# senseBox-HDC1080_v22.net
KiCad netlist of a schematic drawn in EAGLE
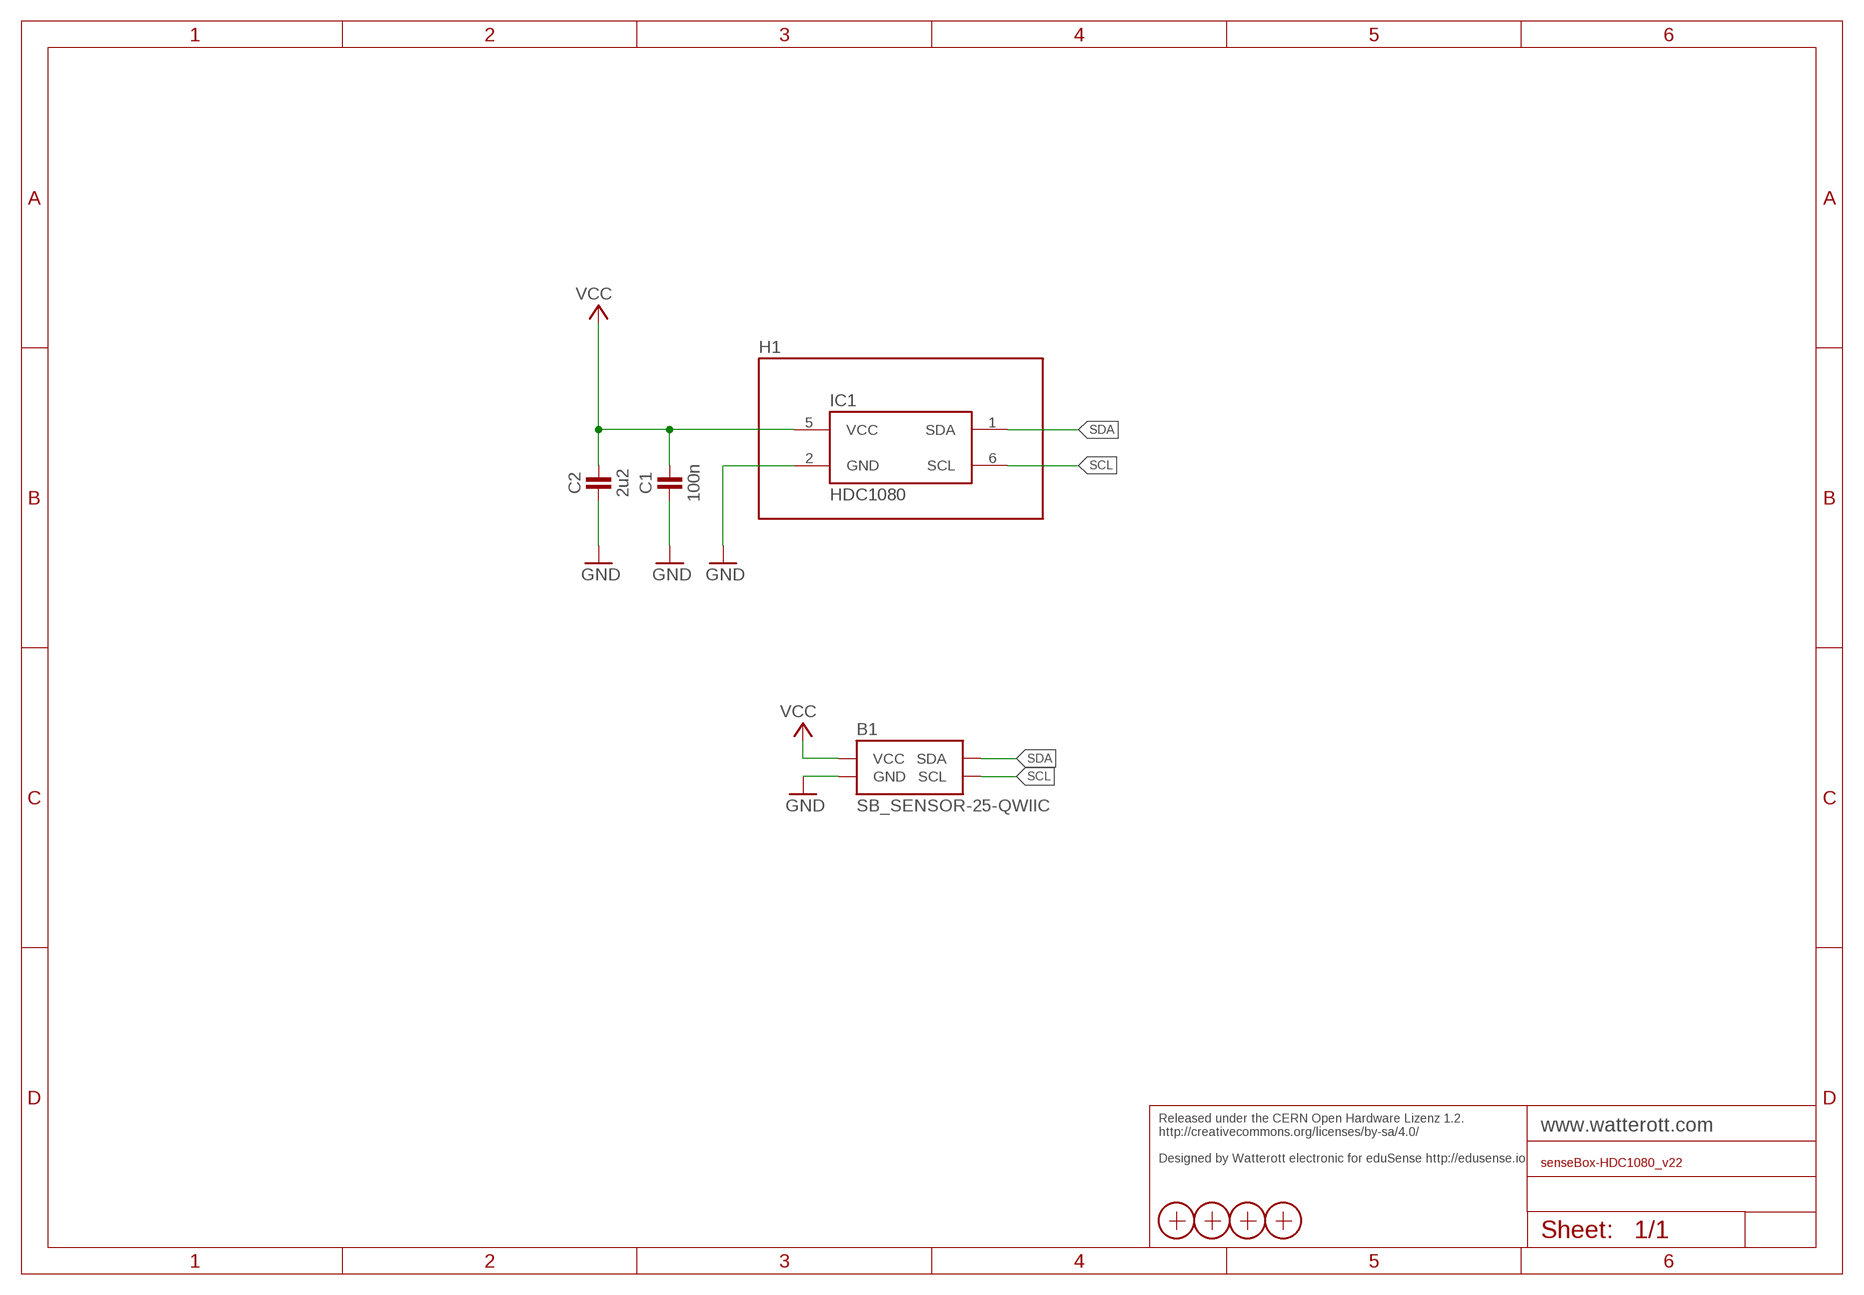
[diagram p0: schematic, sheet 1]

(export (version "E")
  (design (tool "Eeschema 10.0.6"))
  (components
    (comp (ref "B1")
      (value "SB_SENSOR-25-QWIIC")
      (footprint "eagle-import:SB-25X25_QWIIC")
      (libsource (lib "eagle-import") (part "SB_SENSOR-25-QWIIC"))
    )
    (comp (ref "C1")
      (value "100n")
      (footprint "eagle-import:C0402")
      (libsource (lib "eagle-import") (part "CAPACITOR-0402"))
    )
    (comp (ref "C2")
      (value "2u2")
      (footprint "eagle-import:C0402")
      (libsource (lib "eagle-import") (part "CAPACITOR-0402"))
    )
    (comp (ref "H1")
      (value "SF2")
      (footprint "eagle-import:SF2")
      (libsource (lib "eagle-import") (part "SF2"))
    )
    (comp (ref "IC1")
      (value "HDC1080")
      (footprint "eagle-import:WSON6")
      (libsource (lib "eagle-import") (part "HDC1080"))
    )
    (comp (ref "X1")
      (value "PASSER-07")
      (footprint "eagle-import:PASSER_07MM")
      (libsource (lib "eagle-import") (part "PASSER-07"))
    )
    (comp (ref "X2")
      (value "PASSER-07")
      (footprint "eagle-import:PASSER_07MM")
      (libsource (lib "eagle-import") (part "PASSER-07"))
    )
    (comp (ref "X3")
      (value "PASSER-07")
      (footprint "eagle-import:PASSER_07MM")
      (libsource (lib "eagle-import") (part "PASSER-07"))
    )
    (comp (ref "X4")
      (value "PASSER-07")
      (footprint "eagle-import:PASSER_07MM")
      (libsource (lib "eagle-import") (part "PASSER-07"))
    )
  )
  (nets
    (net (code "1") (name "GND") (class "Default")
      (node (ref "B1") (pin "GND@1") (pinfunction "GND_GND@1") (pintype "power_in"))
      (node (ref "B1") (pin "GND@2") (pinfunction "GND_GND@2") (pintype "power_in"))
      (node (ref "B1") (pin "GND@3") (pinfunction "GND_GND@3") (pintype "power_in"))
      (node (ref "C1") (pin "1") (pinfunction "1_1") (pintype "passive"))
      (node (ref "C2") (pin "1") (pinfunction "1_1") (pintype "passive"))
      (node (ref "IC1") (pin "2") (pinfunction "GND_2") (pintype "power_in"))
    )
    (net (code "2") (name "SCL") (class "Default")
      (node (ref "B1") (pin "SCL@1") (pinfunction "SCL_SCL@1") (pintype "bidirectional"))
      (node (ref "B1") (pin "SCL@2") (pinfunction "SCL_SCL@2") (pintype "bidirectional"))
      (node (ref "B1") (pin "SCL@3") (pinfunction "SCL_SCL@3") (pintype "bidirectional"))
      (node (ref "IC1") (pin "6") (pinfunction "SCL_6") (pintype "bidirectional"))
    )
    (net (code "3") (name "SDA") (class "Default")
      (node (ref "B1") (pin "SDA@1") (pinfunction "SDA_SDA@1") (pintype "bidirectional"))
      (node (ref "B1") (pin "SDA@2") (pinfunction "SDA_SDA@2") (pintype "bidirectional"))
      (node (ref "B1") (pin "SDA@3") (pinfunction "SDA_SDA@3") (pintype "bidirectional"))
      (node (ref "IC1") (pin "1") (pinfunction "SDA_1") (pintype "bidirectional"))
    )
    (net (code "4") (name "VCC") (class "Default")
      (node (ref "B1") (pin "VCC@1") (pinfunction "VCC_VCC@1") (pintype "power_in"))
      (node (ref "B1") (pin "VCC@2") (pinfunction "VCC_VCC@2") (pintype "power_in"))
      (node (ref "B1") (pin "VCC@3") (pinfunction "VCC_VCC@3") (pintype "power_in"))
      (node (ref "C1") (pin "2") (pinfunction "2_2") (pintype "passive"))
      (node (ref "C2") (pin "2") (pinfunction "2_2") (pintype "passive"))
      (node (ref "IC1") (pin "5") (pinfunction "VCC_5") (pintype "power_in"))
    )
  )
)
